# ife18_TS_BMS_Master.net
KiCad netlist of a schematic drawn in Altium Designer
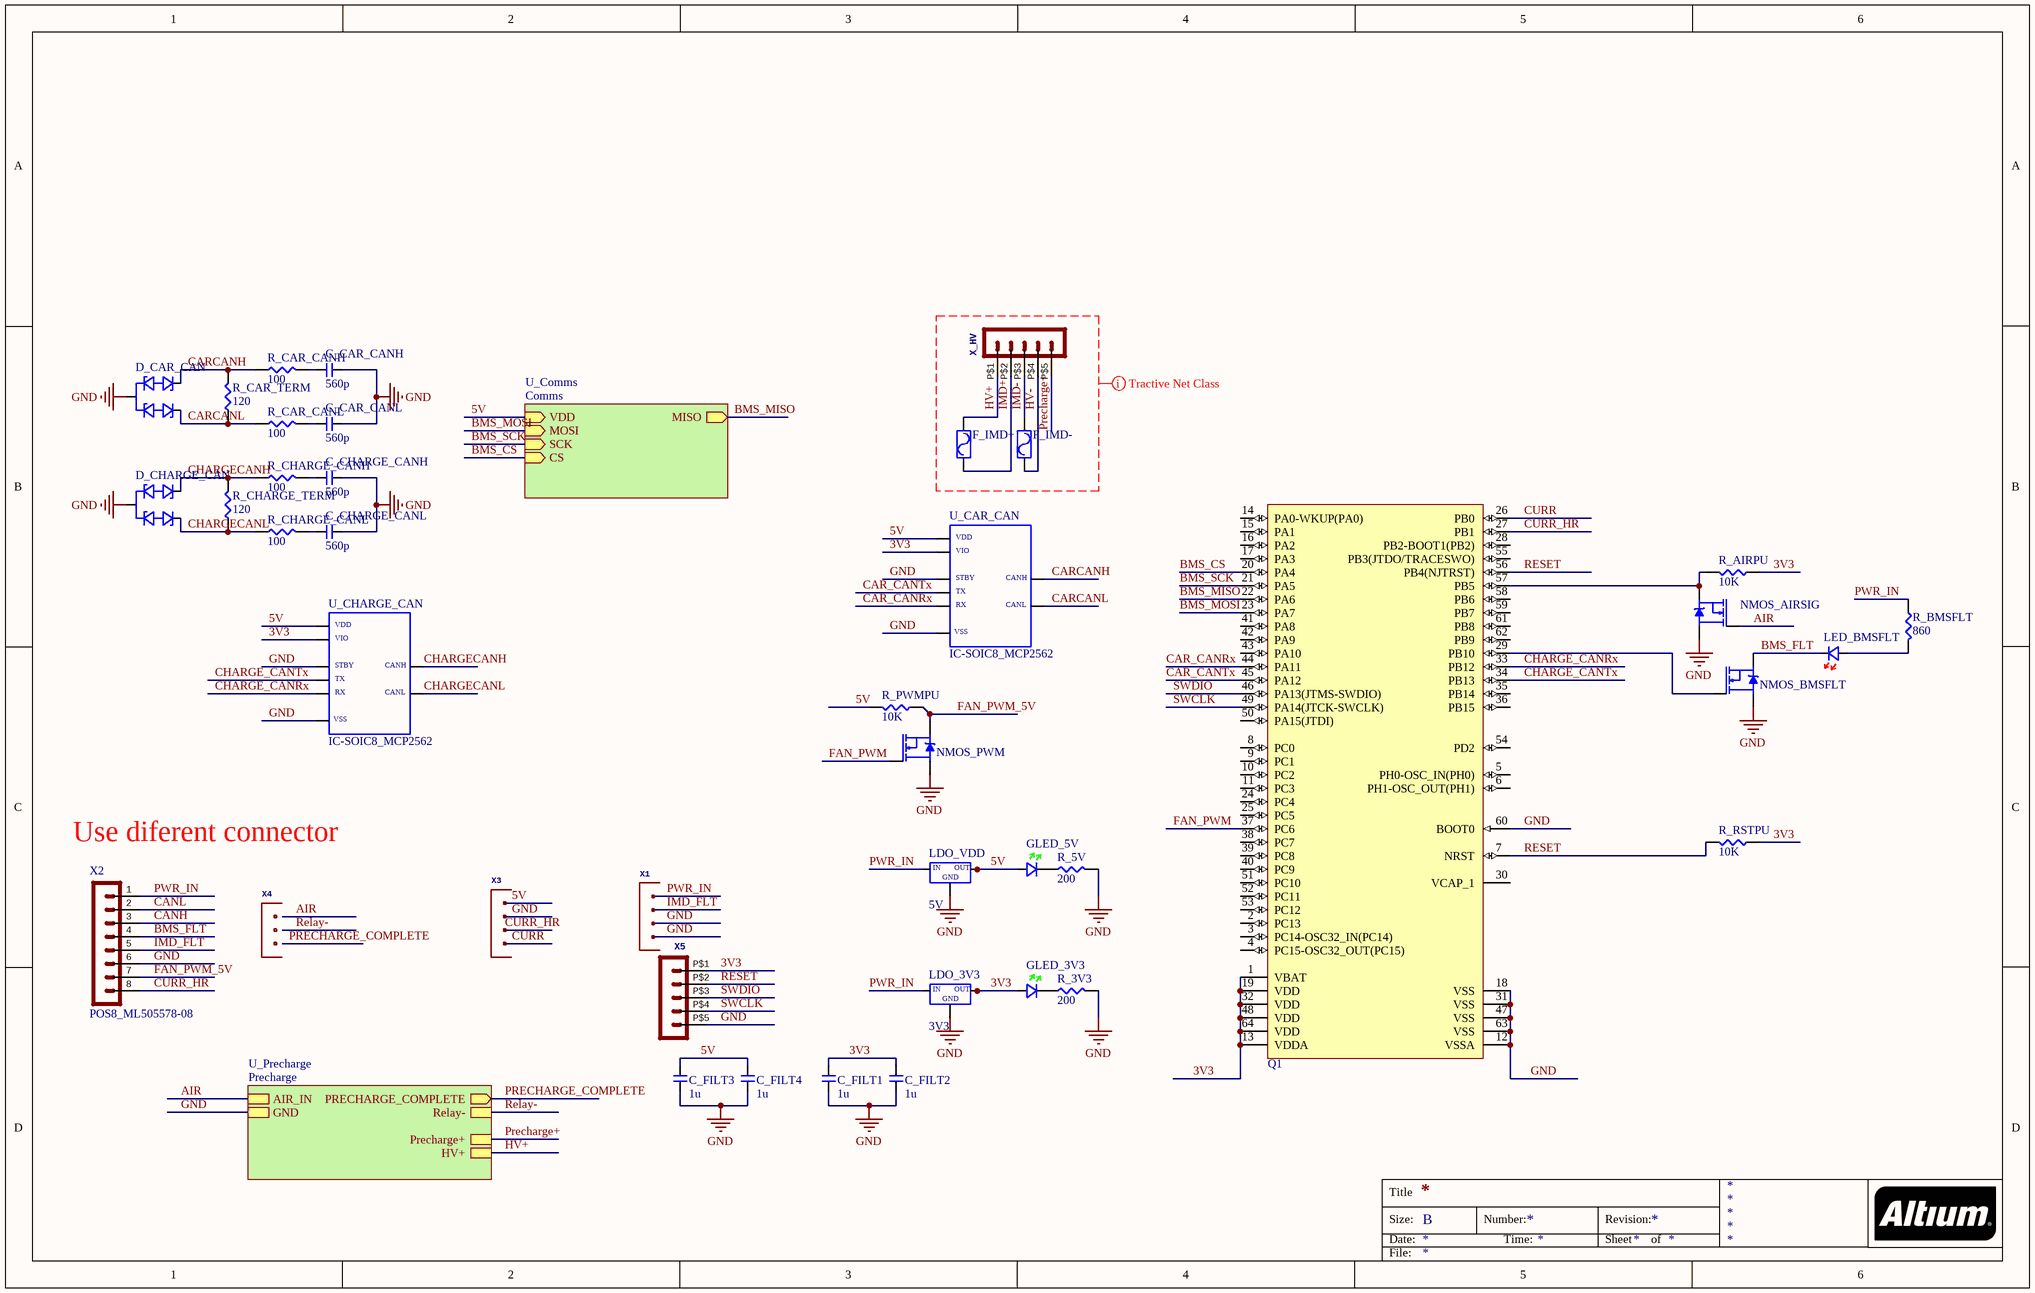
[diagram p0: ife18_TS_BMS_Master.SchDoc]

(export (version "E")
  (design (tool "Eeschema 10.0.6"))
  (components
    (comp (ref "C_CAR_CANH")
      (value "560p")
      (footprint "CAP-0603")
      (libsource (lib "altium-import") (part "root_0_CAP-0603_"))
    )
    (comp (ref "C_CAR_CANL")
      (value "560p")
      (footprint "CAP-0603")
      (libsource (lib "altium-import") (part "root_0_CAP-0603_"))
    )
    (comp (ref "C_CHARGE_CANH")
      (value "560p")
      (footprint "CAP-0603")
      (libsource (lib "altium-import") (part "root_0_CAP-0603_"))
    )
    (comp (ref "C_CHARGE_CANL")
      (value "560p")
      (footprint "CAP-0603")
      (libsource (lib "altium-import") (part "root_0_CAP-0603_"))
    )
    (comp (ref "C_FILT1")
      (value "1u")
      (footprint "CAP-0603")
      (libsource (lib "altium-import") (part "root_1_CAP-0603_"))
    )
    (comp (ref "C_FILT2")
      (value "1u")
      (footprint "CAP-0603")
      (libsource (lib "altium-import") (part "root_1_CAP-0603_"))
    )
    (comp (ref "C_FILT3")
      (value "1u")
      (footprint "CAP-0603")
      (libsource (lib "altium-import") (part "root_1_CAP-0603_"))
    )
    (comp (ref "C_FILT4")
      (value "1u")
      (footprint "CAP-0603")
      (libsource (lib "altium-import") (part "root_1_CAP-0603_"))
    )
    (comp (ref "D_CAR_CAN")
      (value "DIODE-SOT23_PESD1CAN")
      (footprint "SOT23")
      (libsource (lib "altium-import") (part "root_0_DIODE-SOT23_PESD1CAN_"))
    )
    (comp (ref "D_CHARGE_CAN")
      (value "DIODE-SOT23_PESD1CAN")
      (footprint "SOT23")
      (libsource (lib "altium-import") (part "root_0_DIODE-SOT23_PESD1CAN_"))
    )
    (comp (ref "F_IMD+")
      (value "FUSE_885")
      (footprint "FUSE_885")
      (libsource (lib "ife19_Elec_Library") (part "FUSE_885"))
    )
    (comp (ref "F_IMD-")
      (value "FUSE_885")
      (footprint "FUSE_885")
      (libsource (lib "ife19_Elec_Library") (part "FUSE_885"))
    )
    (comp (ref "GLED_3V3")
      (value "~")
      (footprint "LEDGREEN-0603")
      (libsource (lib "altium-import") (part "root_0_LEDGREEN-0603_"))
    )
    (comp (ref "GLED_5V")
      (value "~")
      (footprint "LEDGREEN-0603")
      (libsource (lib "altium-import") (part "root_0_LEDGREEN-0603_"))
    )
    (comp (ref "LDO_3V3")
      (value "3V3")
      (footprint "SOT223")
      (libsource (lib "altium-import") (part "root_0_LDO-SOT223_SPX1117_"))
    )
    (comp (ref "LDO_VDD")
      (value "5V")
      (footprint "SOT223")
      (libsource (lib "altium-import") (part "root_0_LDO-SOT223_SPX1117_"))
    )
    (comp (ref "LED_BMSFLT")
      (value "LEDRED-0603")
      (footprint "LEDRED-0603")
      (libsource (lib "altium-import") (part "root_2_LEDRED-0603_"))
    )
    (comp (ref "NMOS_AIRSIG")
      (value "NMOS-SOT23")
      (footprint "SOT23")
      (libsource (lib "altium-import") (part "root_0_NMOS-SOT23_"))
    )
    (comp (ref "NMOS_BMSFLT")
      (value "NMOS-SOT23")
      (footprint "SOT23")
      (libsource (lib "altium-import") (part "root_0_mirrored_NMOS-SOT23_"))
    )
    (comp (ref "NMOS_PWM")
      (value "NMOS-SOT23")
      (footprint "SOT23")
      (libsource (lib "altium-import") (part "root_0_mirrored_NMOS-SOT23_"))
    )
    (comp (ref "Q1")
      (value "STM32F446RET6")
      (footprint "TSQFP50P1200X1200X160-64N")
      (description "IC MCU 32BIT 512KB FLASH 64LQFP")
      (fields (field (name "MANUFACTURER") "STMicroelectronics"))
      (libsource (lib "ife19_Elec_Library") (part "IC-LQFP64_STM32F446RET6"))
    )
    (comp (ref "R_3V3")
      (value "200")
      (footprint "RES-0603")
      (libsource (lib "altium-import") (part "root_0_RES-0603_"))
    )
    (comp (ref "R_5V")
      (value "200")
      (footprint "RES-0603")
      (libsource (lib "altium-import") (part "root_0_RES-0603_"))
    )
    (comp (ref "R_AIRPU")
      (value "10K")
      (footprint "RES-0603")
      (libsource (lib "altium-import") (part "root_2_RES-0603_"))
    )
    (comp (ref "R_BMSFLT")
      (value "860")
      (footprint "RES-0603")
      (libsource (lib "altium-import") (part "root_1_mirrored_RES-0603_"))
    )
    (comp (ref "R_CAR_CANH")
      (value "100")
      (footprint "RES-0603")
      (libsource (lib "altium-import") (part "root_0_RES-0603_"))
    )
    (comp (ref "R_CAR_CANL")
      (value "100")
      (footprint "RES-0603")
      (libsource (lib "altium-import") (part "root_0_RES-0603_"))
    )
    (comp (ref "R_CAR_TERM")
      (value "120")
      (footprint "RES-0603")
      (libsource (lib "altium-import") (part "root_1_RES-0603_"))
    )
    (comp (ref "R_CHARGE_CANH")
      (value "100")
      (footprint "RES-0603")
      (libsource (lib "altium-import") (part "root_0_RES-0603_"))
    )
    (comp (ref "R_CHARGE_CANL")
      (value "100")
      (footprint "RES-0603")
      (libsource (lib "altium-import") (part "root_0_RES-0603_"))
    )
    (comp (ref "R_CHARGE_TERM")
      (value "120")
      (footprint "RES-0603")
      (libsource (lib "altium-import") (part "root_1_RES-0603_"))
    )
    (comp (ref "R_PWMPU")
      (value "10K")
      (footprint "RES-0603")
      (libsource (lib "altium-import") (part "root_2_mirrored_RES-0603_"))
    )
    (comp (ref "R_RSTPU")
      (value "10K")
      (footprint "RES-0603")
      (libsource (lib "altium-import") (part "root_2_RES-0603_"))
    )
    (comp (ref "U_CAR_CAN")
      (value "IC-SOIC8_MCP2562")
      (footprint "SOIC8")
      (libsource (lib "altium-import") (part "root_0_IC-SOIC8_MCP2562_"))
    )
    (comp (ref "U_CHARGE_CAN")
      (value "IC-SOIC8_MCP2562")
      (footprint "SOIC8")
      (libsource (lib "altium-import") (part "root_0_IC-SOIC8_MCP2562_"))
    )
    (comp (ref "X1")
      (value "Molex 505575-04 4 Position 2.00mm pitch connector wire to board connector Datasheet")
      (footprint "505578-04")
      (fields (field (name "LIBRARYNAME") "MOLEX Micro-Lock"))
      (libsource (lib "ife19_Elec_Conn_Library") (part "POS4_ML505578-04"))
    )
    (comp (ref "X2")
      (value "POS8_ML505578-08")
      (footprint "505575-08")
      (fields (field (name "MANUFACTURER") "Molex") (field (name "MANUFACTURER PART NUMBER") "172065-0308"))
      (libsource (lib "ife19_Elec_Conn_Library") (part "POS8_ML505578-08"))
    )
    (comp (ref "X3")
      (value "Molex 505575-04 4 Position 2.00mm pitch connector wire to board connector Datasheet")
      (footprint "505578-04")
      (fields (field (name "LIBRARYNAME") "MOLEX Micro-Lock"))
      (libsource (lib "ife19_Elec_Conn_Library") (part "POS4_ML505578-04"))
    )
    (comp (ref "X4")
      (value "Molex 505575-03 3 Position 2.00mm pitch connector wire to board connector Datasheet")
      (footprint "505578-03")
      (fields (field (name "LIBRARYNAME") "MOLEX Micro-Lock"))
      (libsource (lib "ife19_Elec_Conn_Library") (part "POS3_ML505578-03"))
    )
    (comp (ref "X5")
      (value "~")
      (footprint "POS5_254MM_MALE")
      (libsource (lib "altium-import") (part "root_0_mirrored_POS5_254MM_MALE_"))
    )
    (comp (ref "X_HV")
      (value "Molex - Micro-Fit 3.0 Series connector,  3.00mm (0.118\") pitch header, 5 positions.")
      (footprint "43650-0524")
      (libsource (lib "ife19_Elec_Conn_Library") (part "POS5_MF43650-0524"))
    )
  )
  (nets
    (net (code "1") (name "/3V3") (class "Default")
      (node (ref "C_FILT1") (pin "2") (pinfunction "2_2") (pintype "passive"))
      (node (ref "C_FILT2") (pin "2") (pinfunction "2_2") (pintype "passive"))
      (node (ref "GLED_3V3") (pin "A") (pinfunction "A_A") (pintype "passive"))
      (node (ref "LDO_3V3") (pin "2") (pinfunction "2_2") (pintype "passive"))
      (node (ref "LDO_3V3") (pin "4") (pinfunction "4_4") (pintype "passive"))
      (node (ref "Q1") (pin "1") (pinfunction "VBAT_1") (pintype "power_in"))
      (node (ref "Q1") (pin "13") (pinfunction "VDDA_13") (pintype "power_in"))
      (node (ref "Q1") (pin "19") (pinfunction "VDD_19") (pintype "power_in"))
      (node (ref "Q1") (pin "32") (pinfunction "VDD_32") (pintype "power_in"))
      (node (ref "Q1") (pin "48") (pinfunction "VDD_48") (pintype "power_in"))
      (node (ref "Q1") (pin "64") (pinfunction "VDD_64") (pintype "power_in"))
      (node (ref "R_AIRPU") (pin "1") (pinfunction "1_1") (pintype "passive"))
      (node (ref "R_RSTPU") (pin "1") (pinfunction "1_1") (pintype "passive"))
      (node (ref "U_CAR_CAN") (pin "5") (pinfunction "5_5") (pintype "passive"))
      (node (ref "U_CHARGE_CAN") (pin "5") (pinfunction "5_5") (pintype "passive"))
      (node (ref "X5") (pin "P$1") (pinfunction "1_P$1") (pintype "passive"))
    )
    (net (code "2") (name "/5V") (class "Default")
      (node (ref "C_FILT3") (pin "2") (pinfunction "2_2") (pintype "passive"))
      (node (ref "C_FILT4") (pin "2") (pinfunction "2_2") (pintype "passive"))
      (node (ref "GLED_5V") (pin "A") (pinfunction "A_A") (pintype "passive"))
      (node (ref "LDO_VDD") (pin "2") (pinfunction "2_2") (pintype "passive"))
      (node (ref "LDO_VDD") (pin "4") (pinfunction "4_4") (pintype "passive"))
      (node (ref "R_PWMPU") (pin "1") (pinfunction "1_1") (pintype "passive"))
      (node (ref "U_CAR_CAN") (pin "3") (pinfunction "3_3") (pintype "passive"))
      (node (ref "U_CHARGE_CAN") (pin "3") (pinfunction "3_3") (pintype "passive"))
      (node (ref "X3") (pin "1") (pinfunction "1_1") (pintype "passive"))
    )
    (net (code "3") (name "/AIR") (class "Default")
      (node (ref "NMOS_AIRSIG") (pin "1") (pinfunction "G_1") (pintype "passive"))
    )
    (net (code "4") (name "/BMS_CS") (class "Default")
      (node (ref "Q1") (pin "20") (pinfunction "PA4_20") (pintype "bidirectional"))
    )
    (net (code "5") (name "/BMS_FLT") (class "Default")
      (node (ref "LED_BMSFLT") (pin "K") (pinfunction "K_K") (pintype "passive"))
      (node (ref "NMOS_BMSFLT") (pin "3") (pinfunction "D_3") (pintype "passive"))
      (node (ref "X2") (pin "4") (pinfunction "4_4") (pintype "passive"))
    )
    (net (code "6") (name "/BMS_MISO") (class "Default")
      (node (ref "Q1") (pin "22") (pinfunction "PA6_22") (pintype "bidirectional"))
    )
    (net (code "7") (name "/BMS_MOSI") (class "Default")
      (node (ref "Q1") (pin "23") (pinfunction "PA7_23") (pintype "bidirectional"))
    )
    (net (code "8") (name "/BMS_SCK") (class "Default")
      (node (ref "Q1") (pin "21") (pinfunction "PA5_21") (pintype "bidirectional"))
    )
    (net (code "9") (name "/CANH") (class "Default")
      (node (ref "X2") (pin "3") (pinfunction "3_3") (pintype "passive"))
    )
    (net (code "10") (name "/CANL") (class "Default")
      (node (ref "X2") (pin "2") (pinfunction "2_2") (pintype "passive"))
    )
    (net (code "11") (name "/CARCANH") (class "Default")
      (node (ref "D_CAR_CAN") (pin "2") (pinfunction "CAN2_2") (pintype "passive"))
      (node (ref "R_CAR_CANH") (pin "1") (pinfunction "1_1") (pintype "passive"))
      (node (ref "R_CAR_TERM") (pin "2") (pinfunction "2_2") (pintype "passive"))
      (node (ref "U_CAR_CAN") (pin "7") (pinfunction "7_7") (pintype "passive"))
    )
    (net (code "12") (name "/CARCANL") (class "Default")
      (node (ref "D_CAR_CAN") (pin "1") (pinfunction "CAN1_1") (pintype "passive"))
      (node (ref "R_CAR_CANL") (pin "1") (pinfunction "1_1") (pintype "passive"))
      (node (ref "R_CAR_TERM") (pin "1") (pinfunction "1_1") (pintype "passive"))
      (node (ref "U_CAR_CAN") (pin "6") (pinfunction "6_6") (pintype "passive"))
    )
    (net (code "13") (name "/CAR_CANRx") (class "Default")
      (node (ref "Q1") (pin "44") (pinfunction "PA11_44") (pintype "bidirectional"))
      (node (ref "U_CAR_CAN") (pin "4") (pinfunction "4_4") (pintype "passive"))
    )
    (net (code "14") (name "/CAR_CANTx") (class "Default")
      (node (ref "Q1") (pin "45") (pinfunction "PA12_45") (pintype "bidirectional"))
      (node (ref "U_CAR_CAN") (pin "1") (pinfunction "1_1") (pintype "passive"))
    )
    (net (code "15") (name "/CHARGECANH") (class "Default")
      (node (ref "D_CHARGE_CAN") (pin "2") (pinfunction "CAN2_2") (pintype "passive"))
      (node (ref "R_CHARGE_CANH") (pin "1") (pinfunction "1_1") (pintype "passive"))
      (node (ref "R_CHARGE_TERM") (pin "2") (pinfunction "2_2") (pintype "passive"))
      (node (ref "U_CHARGE_CAN") (pin "7") (pinfunction "7_7") (pintype "passive"))
    )
    (net (code "16") (name "/CHARGECANL") (class "Default")
      (node (ref "D_CHARGE_CAN") (pin "1") (pinfunction "CAN1_1") (pintype "passive"))
      (node (ref "R_CHARGE_CANL") (pin "1") (pinfunction "1_1") (pintype "passive"))
      (node (ref "R_CHARGE_TERM") (pin "1") (pinfunction "1_1") (pintype "passive"))
      (node (ref "U_CHARGE_CAN") (pin "6") (pinfunction "6_6") (pintype "passive"))
    )
    (net (code "17") (name "/CHARGE_CANRx") (class "Default")
      (node (ref "Q1") (pin "33") (pinfunction "PB12_33") (pintype "bidirectional"))
      (node (ref "U_CHARGE_CAN") (pin "4") (pinfunction "4_4") (pintype "passive"))
    )
    (net (code "18") (name "/CHARGE_CANTx") (class "Default")
      (node (ref "Q1") (pin "34") (pinfunction "PB13_34") (pintype "bidirectional"))
      (node (ref "U_CHARGE_CAN") (pin "1") (pinfunction "1_1") (pintype "passive"))
    )
    (net (code "19") (name "/CURR") (class "Default")
      (node (ref "Q1") (pin "26") (pinfunction "PB0_26") (pintype "bidirectional"))
      (node (ref "X3") (pin "4") (pinfunction "4_4") (pintype "passive"))
    )
    (net (code "20") (name "/CURR_HR") (class "Default")
      (node (ref "Q1") (pin "27") (pinfunction "PB1_27") (pintype "bidirectional"))
      (node (ref "X2") (pin "8") (pinfunction "8_8") (pintype "passive"))
      (node (ref "X3") (pin "3") (pinfunction "3_3") (pintype "passive"))
    )
    (net (code "21") (name "/FAN_PWM") (class "Default")
      (node (ref "NMOS_PWM") (pin "1") (pinfunction "G_1") (pintype "passive"))
      (node (ref "Q1") (pin "37") (pinfunction "PC6_37") (pintype "bidirectional"))
    )
    (net (code "22") (name "/FAN_PWM_5V") (class "Default")
      (node (ref "NMOS_PWM") (pin "3") (pinfunction "D_3") (pintype "passive"))
      (node (ref "R_PWMPU") (pin "2") (pinfunction "2_2") (pintype "passive"))
      (node (ref "X2") (pin "7") (pinfunction "7_7") (pintype "passive"))
    )
    (net (code "23") (name "/HV+") (class "Default")
      (node (ref "F_IMD+") (pin "1") (pinfunction "1_1") (pintype "passive"))
      (node (ref "X_HV") (pin "P$1") (pinfunction "1_P$1") (pintype "passive"))
    )
    (net (code "24") (name "/HV-") (class "Default")
      (node (ref "F_IMD-") (pin "2") (pinfunction "2_2") (pintype "passive"))
      (node (ref "X_HV") (pin "P$4") (pinfunction "4_P$4") (pintype "passive"))
    )
    (net (code "25") (name "/IMD+") (class "Default")
      (node (ref "F_IMD+") (pin "2") (pinfunction "2_2") (pintype "passive"))
      (node (ref "X_HV") (pin "P$2") (pinfunction "2_P$2") (pintype "passive"))
    )
    (net (code "26") (name "/IMD-") (class "Default")
      (node (ref "F_IMD-") (pin "1") (pinfunction "1_1") (pintype "passive"))
      (node (ref "X_HV") (pin "P$3") (pinfunction "3_P$3") (pintype "passive"))
    )
    (net (code "27") (name "/IMD_FLT") (class "Default")
      (node (ref "X1") (pin "2") (pinfunction "2_2") (pintype "passive"))
      (node (ref "X2") (pin "5") (pinfunction "5_5") (pintype "passive"))
    )
    (net (code "29") (name "/PWR_IN") (class "Default")
      (node (ref "LDO_3V3") (pin "3") (pinfunction "3_3") (pintype "passive"))
      (node (ref "LDO_VDD") (pin "3") (pinfunction "3_3") (pintype "passive"))
      (node (ref "R_BMSFLT") (pin "2") (pinfunction "2_2") (pintype "passive"))
      (node (ref "X1") (pin "1") (pinfunction "1_1") (pintype "passive"))
      (node (ref "X2") (pin "1") (pinfunction "1_1") (pintype "passive"))
    )
    (net (code "30") (name "/Precharge+") (class "Default")
      (node (ref "X_HV") (pin "P$5") (pinfunction "5_P$5") (pintype "passive"))
    )
    (net (code "31") (name "/RESET") (class "Default")
      (node (ref "Q1") (pin "56") (pinfunction "PB4(NJTRST)_56") (pintype "bidirectional"))
      (node (ref "Q1") (pin "7") (pinfunction "NRST_7") (pintype "bidirectional"))
      (node (ref "R_RSTPU") (pin "2") (pinfunction "2_2") (pintype "passive"))
      (node (ref "X5") (pin "P$2") (pinfunction "2_P$2") (pintype "passive"))
    )
    (net (code "33") (name "/SWCLK") (class "Default")
      (node (ref "Q1") (pin "49") (pinfunction "PA14(JTCK-SWCLK)_49") (pintype "bidirectional"))
      (node (ref "X5") (pin "P$4") (pinfunction "4_P$4") (pintype "passive"))
    )
    (net (code "34") (name "/SWDIO") (class "Default")
      (node (ref "Q1") (pin "46") (pinfunction "PA13(JTMS-SWDIO)_46") (pintype "bidirectional"))
      (node (ref "X5") (pin "P$3") (pinfunction "3_P$3") (pintype "passive"))
    )
    (net (code "35") (name "GND") (class "Default")
      (node (ref "C_CAR_CANH") (pin "2") (pinfunction "2_2") (pintype "passive"))
      (node (ref "C_CAR_CANL") (pin "2") (pinfunction "2_2") (pintype "passive"))
      (node (ref "C_CHARGE_CANH") (pin "2") (pinfunction "2_2") (pintype "passive"))
      (node (ref "C_CHARGE_CANL") (pin "2") (pinfunction "2_2") (pintype "passive"))
      (node (ref "C_FILT1") (pin "1") (pinfunction "1_1") (pintype "passive"))
      (node (ref "C_FILT2") (pin "1") (pinfunction "1_1") (pintype "passive"))
      (node (ref "C_FILT3") (pin "1") (pinfunction "1_1") (pintype "passive"))
      (node (ref "C_FILT4") (pin "1") (pinfunction "1_1") (pintype "passive"))
      (node (ref "D_CAR_CAN") (pin "3") (pinfunction "G_3") (pintype "passive"))
      (node (ref "D_CHARGE_CAN") (pin "3") (pinfunction "G_3") (pintype "passive"))
      (node (ref "LDO_3V3") (pin "1") (pinfunction "1_1") (pintype "passive"))
      (node (ref "LDO_VDD") (pin "1") (pinfunction "1_1") (pintype "passive"))
      (node (ref "NMOS_AIRSIG") (pin "2") (pinfunction "S_2") (pintype "passive"))
      (node (ref "NMOS_BMSFLT") (pin "2") (pinfunction "S_2") (pintype "passive"))
      (node (ref "NMOS_PWM") (pin "2") (pinfunction "S_2") (pintype "passive"))
      (node (ref "Q1") (pin "12") (pinfunction "VSSA_12") (pintype "power_in"))
      (node (ref "Q1") (pin "18") (pinfunction "VSS_18") (pintype "power_in"))
      (node (ref "Q1") (pin "31") (pinfunction "VSS_31") (pintype "power_in"))
      (node (ref "Q1") (pin "47") (pinfunction "VSS_47") (pintype "power_in"))
      (node (ref "Q1") (pin "60") (pinfunction "BOOT0_60") (pintype "input"))
      (node (ref "Q1") (pin "63") (pinfunction "VSS_63") (pintype "power_in"))
      (node (ref "R_3V3") (pin "2") (pinfunction "2_2") (pintype "passive"))
      (node (ref "R_5V") (pin "2") (pinfunction "2_2") (pintype "passive"))
      (node (ref "U_CAR_CAN") (pin "2") (pinfunction "2_2") (pintype "passive"))
      (node (ref "U_CAR_CAN") (pin "8") (pinfunction "8_8") (pintype "passive"))
      (node (ref "U_CHARGE_CAN") (pin "2") (pinfunction "2_2") (pintype "passive"))
      (node (ref "U_CHARGE_CAN") (pin "8") (pinfunction "8_8") (pintype "passive"))
      (node (ref "X1") (pin "3") (pinfunction "3_3") (pintype "passive"))
      (node (ref "X1") (pin "4") (pinfunction "4_4") (pintype "passive"))
      (node (ref "X2") (pin "6") (pinfunction "6_6") (pintype "passive"))
      (node (ref "X3") (pin "2") (pinfunction "2_2") (pintype "passive"))
      (node (ref "X5") (pin "P$5") (pinfunction "5_P$5") (pintype "passive"))
    )
    (net (code "36") (name "Net-(C_CAR_CANH-Pad1)") (class "Default")
      (node (ref "C_CAR_CANH") (pin "1") (pinfunction "1_1") (pintype "passive"))
      (node (ref "R_CAR_CANH") (pin "2") (pinfunction "2_2") (pintype "passive"))
    )
    (net (code "37") (name "Net-(C_CAR_CANL-Pad1)") (class "Default")
      (node (ref "C_CAR_CANL") (pin "1") (pinfunction "1_1") (pintype "passive"))
      (node (ref "R_CAR_CANL") (pin "2") (pinfunction "2_2") (pintype "passive"))
    )
    (net (code "38") (name "Net-(C_CHARGE_CANH-Pad1)") (class "Default")
      (node (ref "C_CHARGE_CANH") (pin "1") (pinfunction "1_1") (pintype "passive"))
      (node (ref "R_CHARGE_CANH") (pin "2") (pinfunction "2_2") (pintype "passive"))
    )
    (net (code "39") (name "Net-(C_CHARGE_CANL-Pad1)") (class "Default")
      (node (ref "C_CHARGE_CANL") (pin "1") (pinfunction "1_1") (pintype "passive"))
      (node (ref "R_CHARGE_CANL") (pin "2") (pinfunction "2_2") (pintype "passive"))
    )
    (net (code "40") (name "Net-(GLED_3V3-PadK)") (class "Default")
      (node (ref "GLED_3V3") (pin "K") (pinfunction "K_K") (pintype "passive"))
      (node (ref "R_3V3") (pin "1") (pinfunction "1_1") (pintype "passive"))
    )
    (net (code "41") (name "Net-(GLED_5V-PadK)") (class "Default")
      (node (ref "GLED_5V") (pin "K") (pinfunction "K_K") (pintype "passive"))
      (node (ref "R_5V") (pin "1") (pinfunction "1_1") (pintype "passive"))
    )
    (net (code "42") (name "Net-(LED_BMSFLT-PadA)") (class "Default")
      (node (ref "LED_BMSFLT") (pin "A") (pinfunction "A_A") (pintype "passive"))
      (node (ref "R_BMSFLT") (pin "1") (pinfunction "1_1") (pintype "passive"))
    )
    (net (code "43") (name "Net-(NMOS_AIRSIG-D)") (class "Default")
      (node (ref "NMOS_AIRSIG") (pin "3") (pinfunction "D_3") (pintype "passive"))
      (node (ref "Q1") (pin "57") (pinfunction "PB5_57") (pintype "bidirectional"))
      (node (ref "R_AIRPU") (pin "2") (pinfunction "2_2") (pintype "passive"))
    )
    (net (code "44") (name "Net-(NMOS_BMSFLT-G)") (class "Default")
      (node (ref "NMOS_BMSFLT") (pin "1") (pinfunction "G_1") (pintype "passive"))
      (node (ref "Q1") (pin "29") (pinfunction "PB10_29") (pintype "bidirectional"))
    )
    (net (code "45") (name "unconnected-(Q1-PA0-WKUP(PA0)-Pad14)") (class "Default")
      (node (ref "Q1") (pin "14") (pinfunction "PA0-WKUP(PA0)_14") (pintype "bidirectional"))
    )
    (net (code "46") (name "unconnected-(Q1-PA1-Pad15)") (class "Default")
      (node (ref "Q1") (pin "15") (pinfunction "PA1_15") (pintype "bidirectional"))
    )
    (net (code "47") (name "unconnected-(Q1-PA2-Pad16)") (class "Default")
      (node (ref "Q1") (pin "16") (pinfunction "PA2_16") (pintype "bidirectional"))
    )
    (net (code "48") (name "unconnected-(Q1-PA3-Pad17)") (class "Default")
      (node (ref "Q1") (pin "17") (pinfunction "PA3_17") (pintype "bidirectional"))
    )
    (net (code "49") (name "unconnected-(Q1-PA8-Pad41)") (class "Default")
      (node (ref "Q1") (pin "41") (pinfunction "PA8_41") (pintype "bidirectional"))
    )
    (net (code "50") (name "unconnected-(Q1-PA9-Pad42)") (class "Default")
      (node (ref "Q1") (pin "42") (pinfunction "PA9_42") (pintype "bidirectional"))
    )
    (net (code "51") (name "unconnected-(Q1-PA10-Pad43)") (class "Default")
      (node (ref "Q1") (pin "43") (pinfunction "PA10_43") (pintype "bidirectional"))
    )
    (net (code "52") (name "unconnected-(Q1-PA15(JTDI)-Pad50)") (class "Default")
      (node (ref "Q1") (pin "50") (pinfunction "PA15(JTDI)_50") (pintype "bidirectional"))
    )
    (net (code "53") (name "unconnected-(Q1-PB2-BOOT1(PB2)-Pad28)") (class "Default")
      (node (ref "Q1") (pin "28") (pinfunction "PB2-BOOT1(PB2)_28") (pintype "bidirectional"))
    )
    (net (code "54") (name "unconnected-(Q1-PB3(JTDO{slash}TRACESWO)-Pad55)") (class "Default")
      (node (ref "Q1") (pin "55") (pinfunction "PB3(JTDO/TRACESWO)_55") (pintype "bidirectional"))
    )
    (net (code "55") (name "unconnected-(Q1-PB6-Pad58)") (class "Default")
      (node (ref "Q1") (pin "58") (pinfunction "PB6_58") (pintype "bidirectional"))
    )
    (net (code "56") (name "unconnected-(Q1-PB7-Pad59)") (class "Default")
      (node (ref "Q1") (pin "59") (pinfunction "PB7_59") (pintype "bidirectional"))
    )
    (net (code "57") (name "unconnected-(Q1-PB8-Pad61)") (class "Default")
      (node (ref "Q1") (pin "61") (pinfunction "PB8_61") (pintype "bidirectional"))
    )
    (net (code "58") (name "unconnected-(Q1-PB9-Pad62)") (class "Default")
      (node (ref "Q1") (pin "62") (pinfunction "PB9_62") (pintype "bidirectional"))
    )
    (net (code "59") (name "unconnected-(Q1-PB14-Pad35)") (class "Default")
      (node (ref "Q1") (pin "35") (pinfunction "PB14_35") (pintype "bidirectional"))
    )
    (net (code "60") (name "unconnected-(Q1-PB15-Pad36)") (class "Default")
      (node (ref "Q1") (pin "36") (pinfunction "PB15_36") (pintype "bidirectional"))
    )
    (net (code "61") (name "unconnected-(Q1-PC0-Pad8)") (class "Default")
      (node (ref "Q1") (pin "8") (pinfunction "PC0_8") (pintype "bidirectional"))
    )
    (net (code "62") (name "unconnected-(Q1-PC1-Pad9)") (class "Default")
      (node (ref "Q1") (pin "9") (pinfunction "PC1_9") (pintype "bidirectional"))
    )
    (net (code "63") (name "unconnected-(Q1-PC2-Pad10)") (class "Default")
      (node (ref "Q1") (pin "10") (pinfunction "PC2_10") (pintype "bidirectional"))
    )
    (net (code "64") (name "unconnected-(Q1-PC3-Pad11)") (class "Default")
      (node (ref "Q1") (pin "11") (pinfunction "PC3_11") (pintype "bidirectional"))
    )
    (net (code "65") (name "unconnected-(Q1-PC4-Pad24)") (class "Default")
      (node (ref "Q1") (pin "24") (pinfunction "PC4_24") (pintype "bidirectional"))
    )
    (net (code "66") (name "unconnected-(Q1-PC5-Pad25)") (class "Default")
      (node (ref "Q1") (pin "25") (pinfunction "PC5_25") (pintype "bidirectional"))
    )
    (net (code "67") (name "unconnected-(Q1-PC7-Pad38)") (class "Default")
      (node (ref "Q1") (pin "38") (pinfunction "PC7_38") (pintype "bidirectional"))
    )
    (net (code "68") (name "unconnected-(Q1-PC8-Pad39)") (class "Default")
      (node (ref "Q1") (pin "39") (pinfunction "PC8_39") (pintype "bidirectional"))
    )
    (net (code "69") (name "unconnected-(Q1-PC9-Pad40)") (class "Default")
      (node (ref "Q1") (pin "40") (pinfunction "PC9_40") (pintype "bidirectional"))
    )
    (net (code "70") (name "unconnected-(Q1-PC10-Pad51)") (class "Default")
      (node (ref "Q1") (pin "51") (pinfunction "PC10_51") (pintype "bidirectional"))
    )
    (net (code "71") (name "unconnected-(Q1-PC11-Pad52)") (class "Default")
      (node (ref "Q1") (pin "52") (pinfunction "PC11_52") (pintype "bidirectional"))
    )
    (net (code "72") (name "unconnected-(Q1-PC12-Pad53)") (class "Default")
      (node (ref "Q1") (pin "53") (pinfunction "PC12_53") (pintype "bidirectional"))
    )
    (net (code "73") (name "unconnected-(Q1-PC13-Pad2)") (class "Default")
      (node (ref "Q1") (pin "2") (pinfunction "PC13_2") (pintype "bidirectional"))
    )
    (net (code "74") (name "unconnected-(Q1-PC14-OSC32_IN(PC14)-Pad3)") (class "Default")
      (node (ref "Q1") (pin "3") (pinfunction "PC14-OSC32_IN(PC14)_3") (pintype "bidirectional"))
    )
    (net (code "75") (name "unconnected-(Q1-PC15-OSC32_OUT(PC15)-Pad4)") (class "Default")
      (node (ref "Q1") (pin "4") (pinfunction "PC15-OSC32_OUT(PC15)_4") (pintype "bidirectional"))
    )
    (net (code "76") (name "unconnected-(Q1-PD2-Pad54)") (class "Default")
      (node (ref "Q1") (pin "54") (pinfunction "PD2_54") (pintype "bidirectional"))
    )
    (net (code "77") (name "unconnected-(Q1-PH0-OSC_IN(PH0)-Pad5)") (class "Default")
      (node (ref "Q1") (pin "5") (pinfunction "PH0-OSC_IN(PH0)_5") (pintype "bidirectional"))
    )
    (net (code "78") (name "unconnected-(Q1-PH1-OSC_OUT(PH1)-Pad6)") (class "Default")
      (node (ref "Q1") (pin "6") (pinfunction "PH1-OSC_OUT(PH1)_6") (pintype "bidirectional"))
    )
    (net (code "79") (name "unconnected-(Q1-VCAP_1-Pad30)") (class "Default")
      (node (ref "Q1") (pin "30") (pinfunction "VCAP_1_30") (pintype "passive"))
    )
    (net (code "80") (name "unconnected-(X4-Pad1)") (class "Default")
      (node (ref "X4") (pin "1") (pinfunction "1_1") (pintype "passive"))
    )
    (net (code "81") (name "unconnected-(X4-Pad2)") (class "Default")
      (node (ref "X4") (pin "2") (pinfunction "2_2") (pintype "passive"))
    )
    (net (code "82") (name "unconnected-(X4-Pad3)") (class "Default")
      (node (ref "X4") (pin "3") (pinfunction "3_3") (pintype "passive"))
    )
  )
)
